# ADC.net
KiCad netlist of a schematic drawn in Altium Designer
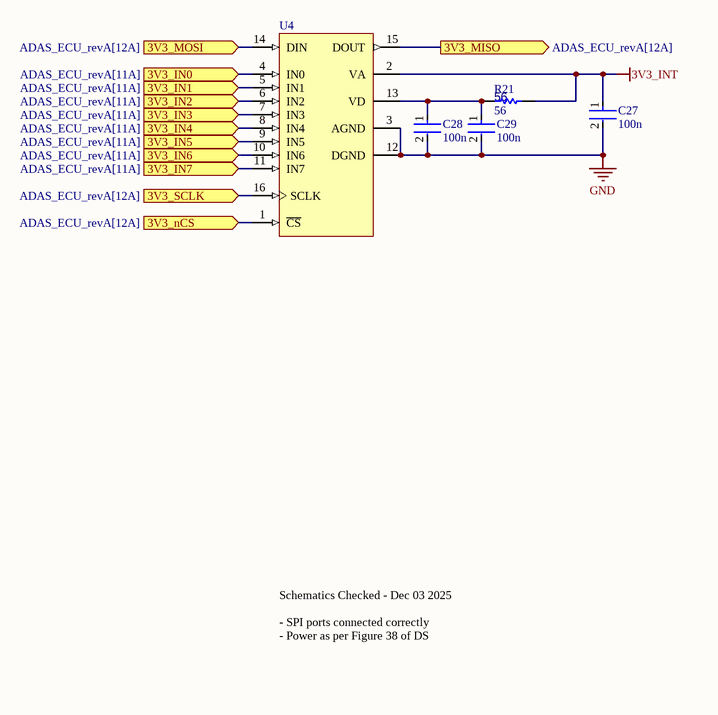
[diagram p0: ADC.SchDoc]

(export (version "E")
  (design (tool "Eeschema 10.0.6"))
  (components
    (comp (ref "C27")
      (value "100n")
      (footprint "FP-0402-L_1_0_0_05-W_0_5-IPC_A")
      (description "LARGE PADS, 0402 CAP, CHANGE COMMENT TO MATCH REAL P/N")
      (libsource (lib "Space Concordia") (part "b4654b650e69147ec39a6b967a45e02"))
    )
    (comp (ref "C28")
      (value "100n")
      (footprint "FP-0402-L_1_0_0_05-W_0_5-IPC_A")
      (description "LARGE PADS, 0402 CAP, CHANGE COMMENT TO MATCH REAL P/N")
      (libsource (lib "Space Concordia") (part "b4654b650e69147ec39a6b967a45e02"))
    )
    (comp (ref "C29")
      (value "100n")
      (footprint "FP-0402-L_1_0_0_05-W_0_5-IPC_A")
      (description "LARGE PADS, 0402 CAP, CHANGE COMMENT TO MATCH REAL P/N")
      (libsource (lib "Space Concordia") (part "b4654b650e69147ec39a6b967a45e02"))
    )
    (comp (ref "R21")
      (value "56")
      (footprint "R0603B")
      (description "Resistor")
      (fields (field (name "ALTIUM_VALUE") "56"))
      (libsource (lib "Space Concordia") (part "Resistor"))
    )
    (comp (ref "U4")
      (value "~")
      (footprint "MTC16_L")
      (description "8-Channel, 50 kSPS to 200 kSPS, 8-Bit A/D Converter, 16-pin TSSOP, Pb-Free")
      (fields (field (name "MANUFACTURER") "National Semiconductor"))
      (libsource (lib "Altium Content Vault") (part "CON-ADC-ADC108S052CIMT"))
    )
  )
  (nets
    (net (code "1") (name "/3V3_IN0") (class "Default")
      (node (ref "U4") (pin "4") (pinfunction "IN0_4") (pintype "input"))
    )
    (net (code "2") (name "/3V3_IN1") (class "Default")
      (node (ref "U4") (pin "5") (pinfunction "IN1_5") (pintype "input"))
    )
    (net (code "3") (name "/3V3_IN2") (class "Default")
      (node (ref "U4") (pin "6") (pinfunction "IN2_6") (pintype "input"))
    )
    (net (code "4") (name "/3V3_IN3") (class "Default")
      (node (ref "U4") (pin "7") (pinfunction "IN3_7") (pintype "input"))
    )
    (net (code "5") (name "/3V3_IN4") (class "Default")
      (node (ref "U4") (pin "8") (pinfunction "IN4_8") (pintype "input"))
    )
    (net (code "6") (name "/3V3_IN5") (class "Default")
      (node (ref "U4") (pin "9") (pinfunction "IN5_9") (pintype "input"))
    )
    (net (code "7") (name "/3V3_IN6") (class "Default")
      (node (ref "U4") (pin "10") (pinfunction "IN6_10") (pintype "input"))
    )
    (net (code "8") (name "/3V3_IN7") (class "Default")
      (node (ref "U4") (pin "11") (pinfunction "IN7_11") (pintype "input"))
    )
    (net (code "9") (name "/3V3_MISO") (class "Default")
      (node (ref "U4") (pin "15") (pinfunction "DOUT_15") (pintype "output"))
    )
    (net (code "10") (name "/3V3_MOSI") (class "Default")
      (node (ref "U4") (pin "14") (pinfunction "DIN_14") (pintype "input"))
    )
    (net (code "11") (name "/3V3_SCLK") (class "Default")
      (node (ref "U4") (pin "16") (pinfunction "SCLK_16") (pintype "input"))
    )
    (net (code "12") (name "/3V3_nCS") (class "Default")
      (node (ref "U4") (pin "1") (pinfunction "~{CS}_1") (pintype "input"))
    )
    (net (code "13") (name "3V3_INT") (class "Default")
      (node (ref "C27") (pin "1") (pinfunction "1_1") (pintype "passive"))
      (node (ref "R21") (pin "1") (pinfunction "1_1") (pintype "passive"))
      (node (ref "U4") (pin "2") (pinfunction "VA_2") (pintype "power_in"))
    )
    (net (code "14") (name "GND") (class "Default")
      (node (ref "C27") (pin "2") (pinfunction "2_2") (pintype "passive"))
      (node (ref "C28") (pin "2") (pinfunction "2_2") (pintype "passive"))
      (node (ref "C29") (pin "2") (pinfunction "2_2") (pintype "passive"))
      (node (ref "U4") (pin "12") (pinfunction "DGND_12") (pintype "power_in"))
      (node (ref "U4") (pin "3") (pinfunction "AGND_3") (pintype "power_in"))
    )
    (net (code "15") (name "Net-(U4-VD)") (class "Default")
      (node (ref "C28") (pin "1") (pinfunction "1_1") (pintype "passive"))
      (node (ref "C29") (pin "1") (pinfunction "1_1") (pintype "passive"))
      (node (ref "R21") (pin "2") (pinfunction "2_2") (pintype "passive"))
      (node (ref "U4") (pin "13") (pinfunction "VD_13") (pintype "power_in"))
    )
  )
)
